# CH32H415REU6-R0.net
KiCad netlist of a schematic drawn in Altium Designer
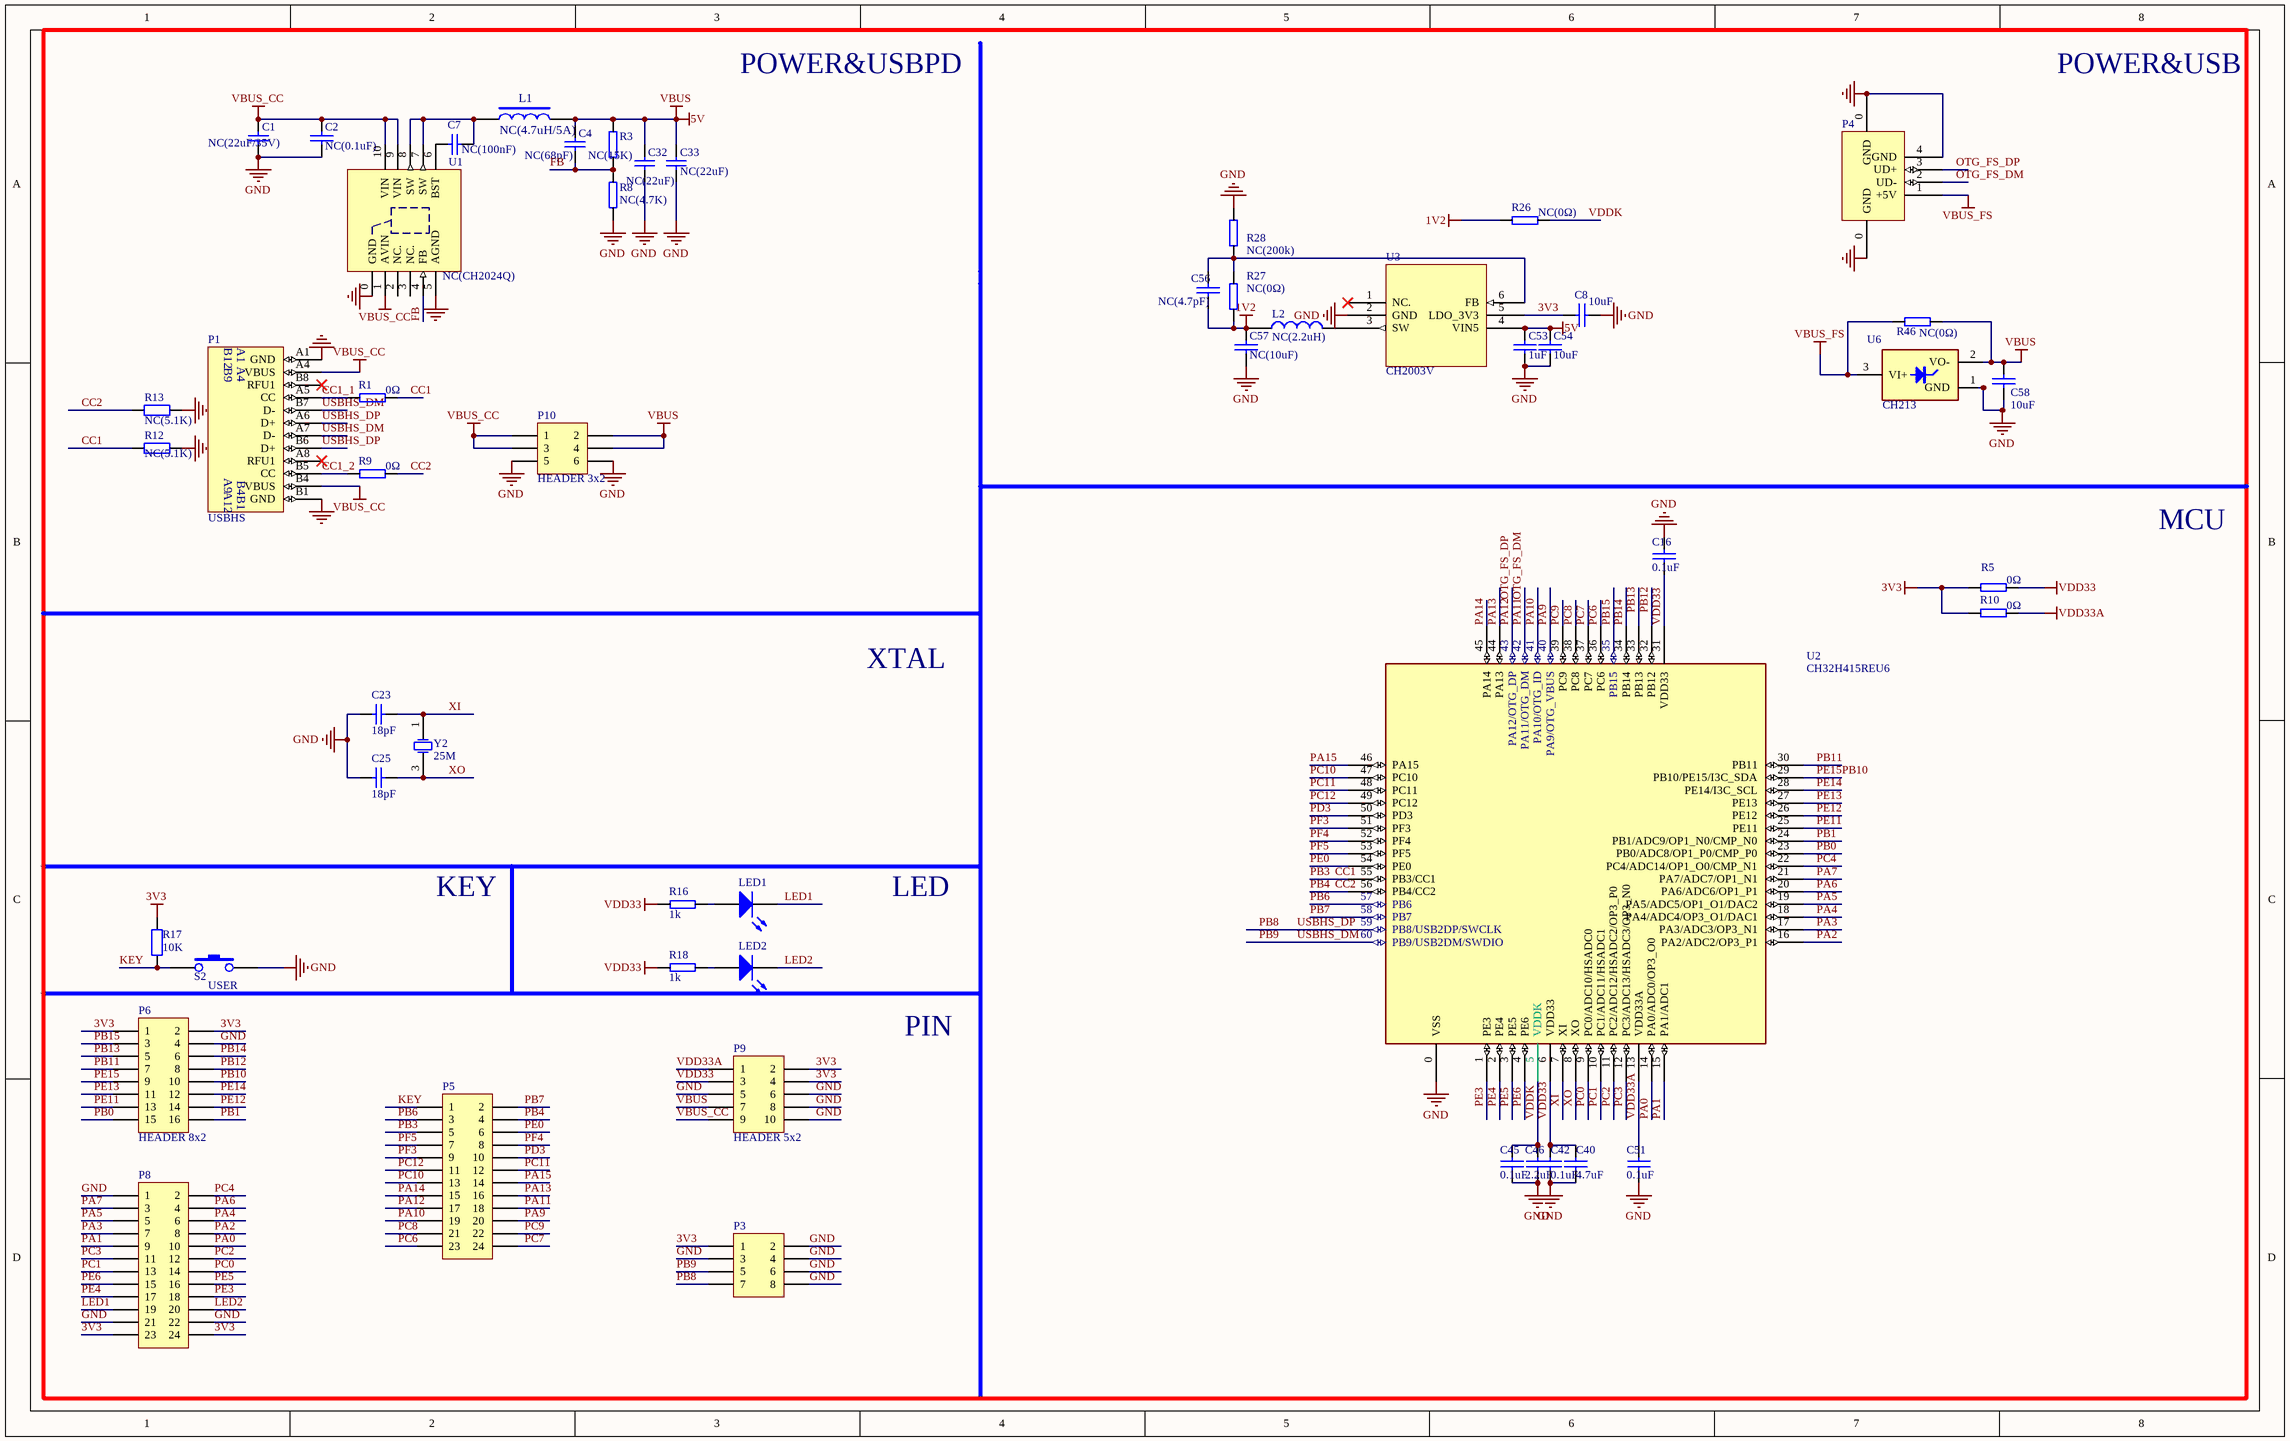
[diagram p0: CH32H415REU6-R0.SchDoc]

(export (version "E")
  (design (tool "Eeschema 10.0.6"))
  (components
    (comp (ref "C1")
      (value "NC(22uF/35V)")
      (footprint "0805_C")
      (description "贴片电容")
      (libsource (lib "Miscellaneous Devices LC") (part "0603 100nF (104) 10% 50V"))
    )
    (comp (ref "C2")
      (value "NC(0.1uF)")
      (footprint "0402_C")
      (description "Capacitor")
      (libsource (lib "") (part "CAP_1"))
    )
    (comp (ref "C4")
      (value "NC(68pF)")
      (footprint "0402_C")
      (description "贴片电容")
      (libsource (lib "Miscellaneous Devices LC") (part "0603 100nF (104) 10% 50V"))
    )
    (comp (ref "C7")
      (value "NC(100nF)")
      (footprint "0603_C")
      (description "贴片电容")
      (libsource (lib "Miscellaneous Devices LC") (part "0603 1uF (105) 10% 50V"))
    )
    (comp (ref "C8")
      (value "10uF")
      (footprint "0603_C")
      (description "Capacitor")
      (libsource (lib "") (part "CAP_1"))
    )
    (comp (ref "C16")
      (value "0.1uF")
      (footprint "0402_C")
      (description "Capacitor")
      (libsource (lib "") (part "CAP_1"))
    )
    (comp (ref "C23")
      (value "18pF")
      (footprint "0402_C")
      (description "Capacitor")
      (libsource (lib "Miscellaneous Devices") (part "Cap"))
    )
    (comp (ref "C25")
      (value "18pF")
      (footprint "0402_C")
      (description "Capacitor")
      (libsource (lib "Miscellaneous Devices") (part "Cap"))
    )
    (comp (ref "C32")
      (value "NC(22uF)")
      (footprint "0805_C")
      (description "贴片电容")
      (libsource (lib "Miscellaneous Devices LC") (part "0603 100nF (104) 10% 50V"))
    )
    (comp (ref "C33")
      (value "NC(22uF)")
      (footprint "0805_C")
      (description "贴片电容")
      (libsource (lib "Miscellaneous Devices LC") (part "0603 100nF (104) 10% 50V"))
    )
    (comp (ref "C40")
      (value "4.7uF")
      (footprint "0402_C")
      (description "Capacitor")
      (libsource (lib "") (part "CAP_1"))
    )
    (comp (ref "C42")
      (value "0.1uF")
      (footprint "0402_C")
      (description "Capacitor")
      (libsource (lib "") (part "CAP_1"))
    )
    (comp (ref "C45")
      (value "0.1uF")
      (footprint "0402_C")
      (description "Capacitor")
      (libsource (lib "") (part "CAP_1"))
    )
    (comp (ref "C46")
      (value "2.2uF")
      (footprint "0402_C")
      (description "Capacitor")
      (libsource (lib "") (part "CAP_1"))
    )
    (comp (ref "C51")
      (value "0.1uF")
      (footprint "0402_C")
      (description "Capacitor")
      (libsource (lib "") (part "CAP_1"))
    )
    (comp (ref "C53")
      (value "1uF")
      (footprint "0402_C")
      (description "Capacitor")
      (libsource (lib "") (part "CAP_2"))
    )
    (comp (ref "C54")
      (value "10uF")
      (footprint "0603_C")
      (description "Capacitor")
      (libsource (lib "") (part "CAP_1"))
    )
    (comp (ref "C56")
      (value "NC(4.7pF)")
      (footprint "0402_C")
      (description "Capacitor")
      (libsource (lib "") (part "CAP_2"))
    )
    (comp (ref "C57")
      (value "NC(10uF)")
      (footprint "0603_C")
      (description "Capacitor")
      (libsource (lib "") (part "CAP_1"))
    )
    (comp (ref "C58")
      (value "10uF")
      (footprint "0603_C")
      (description "Capacitor")
      (libsource (lib "*") (part "CAP"))
    )
    (comp (ref "L1")
      (value "NC(4.7uH/5A)")
      (footprint "SMD_6x6mm")
      (libsource (lib "wch_sch_others") (part "INDUCTOR"))
    )
    (comp (ref "L2") (value "NC(2.2uH)") (footprint "CD32") (libsource (lib "*") (part "INDUCTOR")))
    (comp (ref "LED1")
      (value "LED2  blue")
      (footprint "0603+")
      (description "Typical INFRARED GaAs LED")
      (fields (field (name "PUBLISHER") "Altium Limited"))
      (libsource (lib "Miscellaneous Devices") (part "LED0"))
    )
    (comp (ref "LED2")
      (value "LED1   blue")
      (footprint "0603+")
      (description "Typical INFRARED GaAs LED")
      (fields (field (name "PUBLISHER") "Altium Limited"))
      (libsource (lib "Miscellaneous Devices") (part "LED0"))
    )
    (comp (ref "P1")
      (value "USBHS")
      (footprint "TYPE-C-Receptacle-2.0")
      (libsource (lib "*") (part "TYPE-C1"))
    )
    (comp (ref "P3")
      (value "HEADER 4x2")
      (footprint "MYPCB:IDC8-2.54mm")
      (description "Header, 4-Pin, Dual row")
      (libsource (lib "wch_sch_others") (part "HEADER 4x2"))
    )
    (comp (ref "P4")
      (value "USB_FS")
      (footprint "USBAF")
      (description "USB Port")
      (libsource (lib "*") (part "USB"))
    )
    (comp (ref "P5")
      (value "~")
      (footprint "MYPCB:IDC24-2.54MM")
      (description "Header, 12-Pin, Dual row")
      (libsource (lib "wch_sch_others") (part "HEADER 12x2"))
    )
    (comp (ref "P6")
      (value "HEADER 8x2")
      (footprint "MYPCB:IDC16-2.54mm")
      (description "Header, 8-Pin, Dual row")
      (libsource (lib "wch_sch_others") (part "HEADER 8x2"))
    )
    (comp (ref "P8")
      (value "~")
      (footprint "MYPCB:IDC24-2.54MM")
      (description "Header, 12-Pin, Dual row")
      (libsource (lib "wch_sch_others") (part "HEADER 12x2"))
    )
    (comp (ref "P9")
      (value "HEADER 5x2")
      (footprint "MYPCB:IDC10-2.54mm")
      (description "Header, 5-Pin, Dual row")
      (libsource (lib "wch_sch_others") (part "HEADER 5x2"))
    )
    (comp (ref "P10")
      (value "HEADER 3x2")
      (footprint "MYPCB:IDC6-2.54mm")
      (description "Header, 3-Pin, Dual row")
      (libsource (lib "wch_sch_others") (part "HEADER 3x2"))
    )
    (comp (ref "R1") (value "0Ω") (footprint "0402") (libsource (lib "") (part "RES_1")))
    (comp (ref "R3") (value "NC(15K)") (footprint "0402") (libsource (lib "wch_sch_others(1)") (part "RES")))
    (comp (ref "R5") (value "0Ω") (footprint "0402") (libsource (lib "") (part "RES_1")))
    (comp (ref "R8") (value "NC(4.7K)") (footprint "0402") (libsource (lib "wch_sch_others(1)") (part "RES")))
    (comp (ref "R9") (value "0Ω") (footprint "0402") (libsource (lib "") (part "RES_1")))
    (comp (ref "R10") (value "0Ω") (footprint "0402") (libsource (lib "") (part "RES_1")))
    (comp (ref "R12")
      (value "NC(5.1K)")
      (footprint "0402")
      (description "Resistor")
      (libsource (lib "Miscellaneous Devices") (part "Res2"))
    )
    (comp (ref "R13")
      (value "NC(5.1K)")
      (footprint "0402")
      (description "Resistor")
      (libsource (lib "Miscellaneous Devices") (part "Res2"))
    )
    (comp (ref "R16") (value "1k") (footprint "0402") (libsource (lib "") (part "RES_1")))
    (comp (ref "R17")
      (value "10K")
      (footprint "0402")
      (description "Resistor")
      (libsource (lib "") (part "Res2_1"))
    )
    (comp (ref "R18") (value "1k") (footprint "0402") (libsource (lib "") (part "RES_1")))
    (comp (ref "R26") (value "NC(0Ω)") (footprint "0402") (libsource (lib "") (part "RES_1")))
    (comp (ref "R27") (value "NC(0Ω)") (footprint "0402") (libsource (lib "") (part "RES_1")))
    (comp (ref "R28") (value "NC(200k)") (footprint "0402") (libsource (lib "") (part "RES_1")))
    (comp (ref "R46") (value "NC(0Ω)") (footprint "0402") (libsource (lib "wch_sch_others") (part "RES")))
    (comp (ref "S2")
      (value "USER")
      (footprint "SMD_6.1x3.65x2.5mm-KEY")
      (libsource (lib "wch_sch_others") (part "KEY1"))
    )
    (comp (ref "U1")
      (value "NC(CH2024Q)")
      (footprint "DFN10_3X3")
      (description "Step-Down DC-DC Converter, 28V input, FB 1.2V, 3A output")
      (libsource (lib "DHXXXSCH") (part "CH2024Q"))
    )
    (comp (ref "U2")
      (value "CH32H415REU6")
      (footprint "QFN60_6X6")
      (description "RISC-V FPU HD-MCU, 400MHz, USB2.0 & PD, OPA, ADC, DAC")
      (libsource (lib "DHXXXSCH111") (part "CH32H415REU6"))
    )
    (comp (ref "U3")
      (value "CH2003V")
      (footprint "SOT-23-6")
      (description "Step-Down DC-DC Converter, 5V input, FB 0.6V, 800mA output, with LDO 3.3V * 200mA")
      (libsource (lib "DHXXXSCH") (part "CH2003K"))
    )
    (comp (ref "U6")
      (value "CH213")
      (footprint "SOT-23-3")
      (description "Ideal Diode 5V*1A")
      (libsource (lib "CHXXX") (part "CH213E"))
    )
    (comp (ref "Y2")
      (value "25M")
      (footprint "XT3225")
      (description "Crystal Oscillator")
      (fields (field (name "PUBLISHER") "Altium Limited"))
      (libsource (lib "Miscellaneous Devices") (part "XTAL"))
    )
  )
  (nets
    (net (code "2") (name "/CC1") (class "Default")
      (node (ref "P5") (pin "5") (pinfunction "5_5") (pintype "passive"))
      (node (ref "R1") (pin "1") (pintype "passive"))
      (node (ref "R12") (pin "1") (pinfunction "1_1") (pintype "passive"))
      (node (ref "U2") (pin "55") (pinfunction "PB3/CC1_55") (pintype "bidirectional"))
    )
    (net (code "3") (name "/CC1_1") (class "Default")
      (node (ref "P1") (pin "A5") (pinfunction "CC_A5") (pintype "bidirectional"))
      (node (ref "R1") (pin "2") (pintype "passive"))
    )
    (net (code "4") (name "/CC1_2") (class "Default")
      (node (ref "P1") (pin "B5") (pinfunction "CC_B5") (pintype "bidirectional"))
      (node (ref "R9") (pin "2") (pintype "passive"))
    )
    (net (code "5") (name "/CC2") (class "Default")
      (node (ref "P5") (pin "4") (pinfunction "4_4") (pintype "passive"))
      (node (ref "R13") (pin "1") (pinfunction "1_1") (pintype "passive"))
      (node (ref "R9") (pin "1") (pintype "passive"))
      (node (ref "U2") (pin "56") (pinfunction "PB4/CC2_56") (pintype "bidirectional"))
    )
    (net (code "6") (name "/FB") (class "Default")
      (node (ref "C4") (pin "2") (pinfunction "2_2") (pintype "passive"))
      (node (ref "R3") (pin "1") (pintype "passive"))
      (node (ref "R8") (pin "2") (pintype "passive"))
      (node (ref "U1") (pin "4") (pinfunction "FB_4") (pintype "input"))
    )
    (net (code "7") (name "/KEY") (class "Default")
      (node (ref "P5") (pin "1") (pinfunction "1_1") (pintype "passive"))
      (node (ref "R17") (pin "2") (pinfunction "2_2") (pintype "passive"))
      (node (ref "S2") (pin "1") (pinfunction "1_1") (pintype "passive"))
    )
    (net (code "8") (name "/LED1") (class "Default")
      (node (ref "LED1") (pin "2") (pinfunction "K_2") (pintype "passive"))
      (node (ref "P8") (pin "19") (pinfunction "19_19") (pintype "passive"))
    )
    (net (code "9") (name "/LED2") (class "Default")
      (node (ref "LED2") (pin "2") (pinfunction "K_2") (pintype "passive"))
      (node (ref "P8") (pin "20") (pinfunction "20_20") (pintype "passive"))
    )
    (net (code "10") (name "/OTG_FS_DM") (class "Default")
      (node (ref "P4") (pin "2") (pinfunction "UD-_2") (pintype "bidirectional"))
      (node (ref "P5") (pin "18") (pinfunction "18_18") (pintype "passive"))
      (node (ref "U2") (pin "42") (pinfunction "PA11/OTG_DM_42") (pintype "bidirectional"))
    )
    (net (code "11") (name "/OTG_FS_DP") (class "Default")
      (node (ref "P4") (pin "3") (pinfunction "UD+_3") (pintype "bidirectional"))
      (node (ref "P5") (pin "17") (pinfunction "17_17") (pintype "passive"))
      (node (ref "U2") (pin "43") (pinfunction "PA12/OTG_DP_43") (pintype "bidirectional"))
    )
    (net (code "12") (name "/PA0") (class "Default")
      (node (ref "P8") (pin "10") (pinfunction "10_10") (pintype "passive"))
      (node (ref "U2") (pin "14") (pinfunction "PA0/ADC0/OP3_O0_14") (pintype "bidirectional"))
    )
    (net (code "13") (name "/PA1") (class "Default")
      (node (ref "P8") (pin "9") (pinfunction "9_9") (pintype "passive"))
      (node (ref "U2") (pin "15") (pinfunction "PA1/ADC1_15") (pintype "bidirectional"))
    )
    (net (code "14") (name "/PA2") (class "Default")
      (node (ref "P8") (pin "8") (pinfunction "8_8") (pintype "passive"))
      (node (ref "U2") (pin "16") (pinfunction "PA2/ADC2/OP3_P1_16") (pintype "bidirectional"))
    )
    (net (code "15") (name "/PA3") (class "Default")
      (node (ref "P8") (pin "7") (pinfunction "7_7") (pintype "passive"))
      (node (ref "U2") (pin "17") (pinfunction "PA3/ADC3/OP3_N1_17") (pintype "bidirectional"))
    )
    (net (code "16") (name "/PA4") (class "Default")
      (node (ref "P8") (pin "6") (pinfunction "6_6") (pintype "passive"))
      (node (ref "U2") (pin "18") (pinfunction "PA4/ADC4/OP3_O1/DAC1_18") (pintype "bidirectional"))
    )
    (net (code "17") (name "/PA5") (class "Default")
      (node (ref "P8") (pin "5") (pinfunction "5_5") (pintype "passive"))
      (node (ref "U2") (pin "19") (pinfunction "PA5/ADC5/OP1_O1/DAC2_19") (pintype "bidirectional"))
    )
    (net (code "18") (name "/PA6") (class "Default")
      (node (ref "P8") (pin "4") (pinfunction "4_4") (pintype "passive"))
      (node (ref "U2") (pin "20") (pinfunction "PA6/ADC6/OP1_P1_20") (pintype "bidirectional"))
    )
    (net (code "19") (name "/PA7") (class "Default")
      (node (ref "P8") (pin "3") (pinfunction "3_3") (pintype "passive"))
      (node (ref "U2") (pin "21") (pinfunction "PA7/ADC7/OP1_N1_21") (pintype "bidirectional"))
    )
    (net (code "20") (name "/PA9") (class "Default")
      (node (ref "P5") (pin "20") (pinfunction "20_20") (pintype "passive"))
      (node (ref "U2") (pin "40") (pinfunction "PA9/OTG_VBUS_40") (pintype "bidirectional"))
    )
    (net (code "21") (name "/PA10") (class "Default")
      (node (ref "P5") (pin "19") (pinfunction "19_19") (pintype "passive"))
      (node (ref "U2") (pin "41") (pinfunction "PA10/OTG_ID_41") (pintype "bidirectional"))
    )
    (net (code "22") (name "/PA13") (class "Default")
      (node (ref "P5") (pin "16") (pinfunction "16_16") (pintype "passive"))
      (node (ref "U2") (pin "44") (pinfunction "PA13_44") (pintype "bidirectional"))
    )
    (net (code "23") (name "/PA14") (class "Default")
      (node (ref "P5") (pin "15") (pinfunction "15_15") (pintype "passive"))
      (node (ref "U2") (pin "45") (pinfunction "PA14_45") (pintype "bidirectional"))
    )
    (net (code "24") (name "/PA15") (class "Default")
      (node (ref "P5") (pin "14") (pinfunction "14_14") (pintype "passive"))
      (node (ref "U2") (pin "46") (pinfunction "PA15_46") (pintype "bidirectional"))
    )
    (net (code "25") (name "/PB0") (class "Default")
      (node (ref "P6") (pin "15") (pinfunction "15_15") (pintype "passive"))
      (node (ref "U2") (pin "23") (pinfunction "PB0/ADC8/OP1_P0/CMP_P0_23") (pintype "bidirectional"))
    )
    (net (code "26") (name "/PB1") (class "Default")
      (node (ref "P6") (pin "16") (pinfunction "16_16") (pintype "passive"))
      (node (ref "U2") (pin "24") (pinfunction "PB1/ADC9/OP1_N0/CMP_N0_24") (pintype "bidirectional"))
    )
    (net (code "27") (name "/PB6") (class "Default")
      (node (ref "P5") (pin "3") (pinfunction "3_3") (pintype "passive"))
      (node (ref "U2") (pin "57") (pinfunction "PB6_57") (pintype "bidirectional"))
    )
    (net (code "28") (name "/PB7") (class "Default")
      (node (ref "P5") (pin "2") (pinfunction "2_2") (pintype "passive"))
      (node (ref "U2") (pin "58") (pinfunction "PB7_58") (pintype "bidirectional"))
    )
    (net (code "29") (name "/PB8") (class "Default")
      (node (ref "P1") (pin "A6") (pinfunction "D+_A6") (pintype "bidirectional"))
      (node (ref "P1") (pin "B6") (pinfunction "D+_B6") (pintype "bidirectional"))
      (node (ref "P3") (pin "7") (pinfunction "7_7") (pintype "passive"))
      (node (ref "U2") (pin "59") (pinfunction "PB8/USB2DP/SWCLK_59") (pintype "bidirectional"))
    )
    (net (code "30") (name "/PB9") (class "Default")
      (node (ref "P1") (pin "A7") (pinfunction "D-_A7") (pintype "bidirectional"))
      (node (ref "P1") (pin "B7") (pinfunction "D-_B7") (pintype "bidirectional"))
      (node (ref "P3") (pin "5") (pinfunction "5_5") (pintype "passive"))
      (node (ref "U2") (pin "60") (pinfunction "PB9/USB2DM/SWDIO_60") (pintype "bidirectional"))
    )
    (net (code "31") (name "/PB10") (class "Default")
      (node (ref "P6") (pin "10") (pinfunction "10_10") (pintype "passive"))
      (node (ref "P6") (pin "9") (pinfunction "9_9") (pintype "passive"))
      (node (ref "U2") (pin "29") (pinfunction "PB10/PE15/I3C_SDA_29") (pintype "bidirectional"))
    )
    (net (code "32") (name "/PB11") (class "Default")
      (node (ref "P6") (pin "7") (pinfunction "7_7") (pintype "passive"))
      (node (ref "U2") (pin "30") (pinfunction "PB11_30") (pintype "bidirectional"))
    )
    (net (code "33") (name "/PB12") (class "Default")
      (node (ref "P6") (pin "8") (pinfunction "8_8") (pintype "passive"))
      (node (ref "U2") (pin "32") (pinfunction "PB12_32") (pintype "bidirectional"))
    )
    (net (code "34") (name "/PB13") (class "Default")
      (node (ref "P6") (pin "5") (pinfunction "5_5") (pintype "passive"))
      (node (ref "U2") (pin "33") (pinfunction "PB13_33") (pintype "bidirectional"))
    )
    (net (code "35") (name "/PB14") (class "Default")
      (node (ref "P6") (pin "6") (pinfunction "6_6") (pintype "passive"))
      (node (ref "U2") (pin "34") (pinfunction "PB14_34") (pintype "bidirectional"))
    )
    (net (code "36") (name "/PB15") (class "Default")
      (node (ref "P6") (pin "3") (pinfunction "3_3") (pintype "passive"))
      (node (ref "U2") (pin "35") (pinfunction "PB15_35") (pintype "bidirectional"))
    )
    (net (code "37") (name "/PC0") (class "Default")
      (node (ref "P8") (pin "14") (pinfunction "14_14") (pintype "passive"))
      (node (ref "U2") (pin "9") (pinfunction "PC0/ADC10/HSADC0_9") (pintype "bidirectional"))
    )
    (net (code "38") (name "/PC1") (class "Default")
      (node (ref "P8") (pin "13") (pinfunction "13_13") (pintype "passive"))
      (node (ref "U2") (pin "10") (pinfunction "PC1/ADC11/HSADC1_10") (pintype "bidirectional"))
    )
    (net (code "39") (name "/PC2") (class "Default")
      (node (ref "P8") (pin "12") (pinfunction "12_12") (pintype "passive"))
      (node (ref "U2") (pin "11") (pinfunction "PC2/ADC12/HSADC2/OP3_P0_11") (pintype "bidirectional"))
    )
    (net (code "40") (name "/PC3") (class "Default")
      (node (ref "P8") (pin "11") (pinfunction "11_11") (pintype "passive"))
      (node (ref "U2") (pin "12") (pinfunction "PC3/ADC13/HSADC3/OP3_N0_12") (pintype "bidirectional"))
    )
    (net (code "41") (name "/PC4") (class "Default")
      (node (ref "P8") (pin "2") (pinfunction "2_2") (pintype "passive"))
      (node (ref "U2") (pin "22") (pinfunction "PC4/ADC14/OP1_O0/CMP_N1_22") (pintype "bidirectional"))
    )
    (net (code "42") (name "/PC6") (class "Default")
      (node (ref "P5") (pin "23") (pinfunction "23_23") (pintype "passive"))
      (node (ref "U2") (pin "36") (pinfunction "PC6_36") (pintype "bidirectional"))
    )
    (net (code "43") (name "/PC7") (class "Default")
      (node (ref "P5") (pin "24") (pinfunction "24_24") (pintype "passive"))
      (node (ref "U2") (pin "37") (pinfunction "PC7_37") (pintype "bidirectional"))
    )
    (net (code "44") (name "/PC8") (class "Default")
      (node (ref "P5") (pin "21") (pinfunction "21_21") (pintype "passive"))
      (node (ref "U2") (pin "38") (pinfunction "PC8_38") (pintype "bidirectional"))
    )
    (net (code "45") (name "/PC9") (class "Default")
      (node (ref "P5") (pin "22") (pinfunction "22_22") (pintype "passive"))
      (node (ref "U2") (pin "39") (pinfunction "PC9_39") (pintype "bidirectional"))
    )
    (net (code "46") (name "/PC10") (class "Default")
      (node (ref "P5") (pin "13") (pinfunction "13_13") (pintype "passive"))
      (node (ref "U2") (pin "47") (pinfunction "PC10_47") (pintype "bidirectional"))
    )
    (net (code "47") (name "/PC11") (class "Default")
      (node (ref "P5") (pin "12") (pinfunction "12_12") (pintype "passive"))
      (node (ref "U2") (pin "48") (pinfunction "PC11_48") (pintype "bidirectional"))
    )
    (net (code "48") (name "/PC12") (class "Default")
      (node (ref "P5") (pin "11") (pinfunction "11_11") (pintype "passive"))
      (node (ref "U2") (pin "49") (pinfunction "PC12_49") (pintype "bidirectional"))
    )
    (net (code "49") (name "/PD3") (class "Default")
      (node (ref "P5") (pin "10") (pinfunction "10_10") (pintype "passive"))
      (node (ref "U2") (pin "50") (pinfunction "PD3_50") (pintype "bidirectional"))
    )
    (net (code "50") (name "/PE0") (class "Default")
      (node (ref "P5") (pin "6") (pinfunction "6_6") (pintype "passive"))
      (node (ref "U2") (pin "54") (pinfunction "PE0_54") (pintype "bidirectional"))
    )
    (net (code "51") (name "/PE3") (class "Default")
      (node (ref "P8") (pin "18") (pinfunction "18_18") (pintype "passive"))
      (node (ref "U2") (pin "1") (pinfunction "PE3_1") (pintype "bidirectional"))
    )
    (net (code "52") (name "/PE4") (class "Default")
      (node (ref "P8") (pin "17") (pinfunction "17_17") (pintype "passive"))
      (node (ref "U2") (pin "2") (pinfunction "PE4_2") (pintype "bidirectional"))
    )
    (net (code "53") (name "/PE5") (class "Default")
      (node (ref "P8") (pin "16") (pinfunction "16_16") (pintype "passive"))
      (node (ref "U2") (pin "3") (pinfunction "PE5_3") (pintype "bidirectional"))
    )
    (net (code "54") (name "/PE6") (class "Default")
      (node (ref "P8") (pin "15") (pinfunction "15_15") (pintype "passive"))
      (node (ref "U2") (pin "4") (pinfunction "PE6_4") (pintype "bidirectional"))
    )
    (net (code "55") (name "/PE11") (class "Default")
      (node (ref "P6") (pin "13") (pinfunction "13_13") (pintype "passive"))
      (node (ref "U2") (pin "25") (pinfunction "PE11_25") (pintype "bidirectional"))
    )
    (net (code "56") (name "/PE12") (class "Default")
      (node (ref "P6") (pin "14") (pinfunction "14_14") (pintype "passive"))
      (node (ref "U2") (pin "26") (pinfunction "PE12_26") (pintype "bidirectional"))
    )
    (net (code "57") (name "/PE13") (class "Default")
      (node (ref "P6") (pin "11") (pinfunction "11_11") (pintype "passive"))
      (node (ref "U2") (pin "27") (pinfunction "PE13_27") (pintype "bidirectional"))
    )
    (net (code "58") (name "/PE14") (class "Default")
      (node (ref "P6") (pin "12") (pinfunction "12_12") (pintype "passive"))
      (node (ref "U2") (pin "28") (pinfunction "PE14/I3C_SCL_28") (pintype "bidirectional"))
    )
    (net (code "59") (name "/PF3") (class "Default")
      (node (ref "P5") (pin "9") (pinfunction "9_9") (pintype "passive"))
      (node (ref "U2") (pin "51") (pinfunction "PF3_51") (pintype "bidirectional"))
    )
    (net (code "60") (name "/PF4") (class "Default")
      (node (ref "P5") (pin "8") (pinfunction "8_8") (pintype "passive"))
      (node (ref "U2") (pin "52") (pinfunction "PF4_52") (pintype "bidirectional"))
    )
    (net (code "61") (name "/PF5") (class "Default")
      (node (ref "P5") (pin "7") (pinfunction "7_7") (pintype "passive"))
      (node (ref "U2") (pin "53") (pinfunction "PF5_53") (pintype "bidirectional"))
    )
    (net (code "62") (name "/VDDK") (class "Default")
      (node (ref "C45") (pin "2") (pinfunction "2_2") (pintype "passive"))
      (node (ref "C46") (pin "1") (pinfunction "1_1") (pintype "passive"))
      (node (ref "R26") (pin "1") (pintype "passive"))
      (node (ref "U2") (pin "5") (pinfunction "VDDK_5") (pintype "power_in"))
    )
    (net (code "63") (name "/XI") (class "Default")
      (node (ref "C23") (pin "2") (pinfunction "2_2") (pintype "passive"))
      (node (ref "U2") (pin "7") (pinfunction "XI_7") (pintype "bidirectional"))
      (node (ref "Y2") (pin "1") (pinfunction "OSC1_1") (pintype "passive"))
    )
    (net (code "64") (name "/XO") (class "Default")
      (node (ref "C25") (pin "2") (pinfunction "2_2") (pintype "passive"))
      (node (ref "U2") (pin "8") (pinfunction "XO_8") (pintype "bidirectional"))
      (node (ref "Y2") (pin "3") (pinfunction "OSC2_3") (pintype "passive"))
    )
    (net (code "65") (name "1V2") (class "Default")
      (node (ref "C56") (pin "1") (pinfunction "1_1") (pintype "passive"))
      (node (ref "C57") (pin "2") (pinfunction "2_2") (pintype "passive"))
      (node (ref "L2") (pin "2") (pinfunction "2_2") (pintype "passive"))
      (node (ref "R26") (pin "2") (pintype "passive"))
      (node (ref "R27") (pin "1") (pintype "passive"))
    )
    (net (code "66") (name "3V3") (class "Default")
      (node (ref "C8") (pin "2") (pinfunction "2_2") (pintype "passive"))
      (node (ref "P3") (pin "1") (pinfunction "1_1") (pintype "passive"))
      (node (ref "P6") (pin "1") (pinfunction "1_1") (pintype "passive"))
      (node (ref "P6") (pin "2") (pinfunction "2_2") (pintype "passive"))
      (node (ref "P8") (pin "23") (pinfunction "23_23") (pintype "passive"))
      (node (ref "P8") (pin "24") (pinfunction "24_24") (pintype "passive"))
      (node (ref "P9") (pin "2") (pinfunction "2_2") (pintype "passive"))
      (node (ref "P9") (pin "4") (pinfunction "4_4") (pintype "passive"))
      (node (ref "R10") (pin "2") (pintype "passive"))
      (node (ref "R17") (pin "1") (pinfunction "1_1") (pintype "passive"))
      (node (ref "R5") (pin "2") (pintype "passive"))
      (node (ref "U3") (pin "5") (pinfunction "LDO_3V3_5") (pintype "power_in"))
    )
    (net (code "67") (name "5V") (class "Default")
      (node (ref "C32") (pin "2") (pinfunction "2_2") (pintype "passive"))
      (node (ref "C33") (pin "2") (pinfunction "2_2") (pintype "passive"))
      (node (ref "C4") (pin "1") (pinfunction "1_1") (pintype "passive"))
      (node (ref "C53") (pin "2") (pinfunction "2_2") (pintype "passive"))
      (node (ref "C54") (pin "2") (pinfunction "2_2") (pintype "passive"))
      (node (ref "C58") (pin "1") (pinfunction "1_1") (pintype "passive"))
      (node (ref "L1") (pin "2") (pinfunction "2_2") (pintype "passive"))
      (node (ref "P10") (pin "2") (pinfunction "2_2") (pintype "passive"))
      (node (ref "P10") (pin "4") (pinfunction "4_4") (pintype "passive"))
      (node (ref "P9") (pin "7") (pinfunction "7_7") (pintype "passive"))
      (node (ref "R3") (pin "2") (pintype "passive"))
      (node (ref "R46") (pin "1") (pintype "passive"))
      (node (ref "U3") (pin "4") (pinfunction "VIN5_4") (pintype "power_in"))
      (node (ref "U6") (pin "2") (pinfunction "VO-_2") (pintype "power_in"))
    )
    (net (code "68") (name "GND") (class "Default")
      (node (ref "C1") (pin "1") (pinfunction "1_1") (pintype "passive"))
      (node (ref "C16") (pin "2") (pinfunction "2_2") (pintype "passive"))
      (node (ref "C2") (pin "1") (pinfunction "1_1") (pintype "passive"))
      (node (ref "C23") (pin "1") (pinfunction "1_1") (pintype "passive"))
      (node (ref "C25") (pin "1") (pinfunction "1_1") (pintype "passive"))
      (node (ref "C32") (pin "1") (pinfunction "1_1") (pintype "passive"))
      (node (ref "C33") (pin "1") (pinfunction "1_1") (pintype "passive"))
      (node (ref "C40") (pin "1") (pinfunction "1_1") (pintype "passive"))
      (node (ref "C42") (pin "1") (pinfunction "1_1") (pintype "passive"))
      (node (ref "C45") (pin "1") (pinfunction "1_1") (pintype "passive"))
      (node (ref "C46") (pin "2") (pinfunction "2_2") (pintype "passive"))
      (node (ref "C51") (pin "1") (pinfunction "1_1") (pintype "passive"))
      (node (ref "C53") (pin "1") (pinfunction "1_1") (pintype "passive"))
      (node (ref "C54") (pin "1") (pinfunction "1_1") (pintype "passive"))
      (node (ref "C57") (pin "1") (pinfunction "1_1") (pintype "passive"))
      (node (ref "C58") (pin "2") (pinfunction "2_2") (pintype "passive"))
      (node (ref "C8") (pin "1") (pinfunction "1_1") (pintype "passive"))
      (node (ref "P1") (pin "A1") (pinfunction "GND_A1") (pintype "bidirectional"))
      (node (ref "P1") (pin "B1") (pinfunction "GND_B1") (pintype "bidirectional"))
      (node (ref "P10") (pin "5") (pinfunction "5_5") (pintype "passive"))
      (node (ref "P10") (pin "6") (pinfunction "6_6") (pintype "passive"))
      (node (ref "P3") (pin "2") (pinfunction "2_2") (pintype "passive"))
      (node (ref "P3") (pin "3") (pinfunction "3_3") (pintype "passive"))
      (node (ref "P3") (pin "4") (pinfunction "4_4") (pintype "passive"))
      (node (ref "P3") (pin "6") (pinfunction "6_6") (pintype "passive"))
      (node (ref "P3") (pin "8") (pinfunction "8_8") (pintype "passive"))
      (node (ref "P4") (pin "0") (pinfunction "GND_0") (pintype "power_in"))
      (node (ref "P4") (pin "4") (pinfunction "GND_4") (pintype "power_in"))
      (node (ref "P6") (pin "4") (pinfunction "4_4") (pintype "passive"))
      (node (ref "P8") (pin "1") (pinfunction "1_1") (pintype "passive"))
      (node (ref "P8") (pin "21") (pinfunction "21_21") (pintype "passive"))
      (node (ref "P8") (pin "22") (pinfunction "22_22") (pintype "passive"))
      (node (ref "P9") (pin "10") (pinfunction "10_10") (pintype "passive"))
      (node (ref "P9") (pin "5") (pinfunction "5_5") (pintype "passive"))
      (node (ref "P9") (pin "6") (pinfunction "6_6") (pintype "passive"))
      (node (ref "P9") (pin "8") (pinfunction "8_8") (pintype "passive"))
      (node (ref "R12") (pin "2") (pinfunction "2_2") (pintype "passive"))
      (node (ref "R13") (pin "2") (pinfunction "2_2") (pintype "passive"))
      (node (ref "R28") (pin "2") (pintype "passive"))
      (node (ref "R8") (pin "1") (pintype "passive"))
      (node (ref "S2") (pin "2") (pinfunction "2_2") (pintype "passive"))
      (node (ref "U1") (pin "0") (pinfunction "GND_0") (pintype "power_in"))
      (node (ref "U1") (pin "5") (pinfunction "AGND_5") (pintype "power_in"))
      (node (ref "U2") (pin "0") (pinfunction "VSS_0") (pintype "power_in"))
      (node (ref "U3") (pin "2") (pinfunction "GND_2") (pintype "power_in"))
      (node (ref "U6") (pin "1") (pinfunction "GND_1") (pintype "power_in"))
    )
    (net (code "69") (name "Net-(C7-Pad2)") (class "Default")
      (node (ref "C7") (pin "2") (pinfunction "2_2") (pintype "passive"))
      (node (ref "L1") (pin "1") (pinfunction "1_1") (pintype "passive"))
      (node (ref "U1") (pin "7") (pinfunction "SW_7") (pintype "output"))
      (node (ref "U1") (pin "8") (pinfunction "SW_8") (pintype "output"))
    )
    (net (code "70") (name "Net-(LED1-A)") (class "Default")
      (node (ref "LED1") (pin "1") (pinfunction "A_1") (pintype "passive"))
      (node (ref "R16") (pin "2") (pintype "passive"))
    )
    (net (code "71") (name "Net-(LED2-A)") (class "Default")
      (node (ref "LED2") (pin "1") (pinfunction "A_1") (pintype "passive"))
      (node (ref "R18") (pin "2") (pintype "passive"))
    )
    (net (code "72") (name "Net-(U1-BST)") (class "Default")
      (node (ref "C7") (pin "1") (pinfunction "1_1") (pintype "passive"))
      (node (ref "U1") (pin "6") (pinfunction "BST_6") (pintype "power_in"))
    )
    (net (code "73") (name "Net-(U3-FB)") (class "Default")
      (node (ref "C56") (pin "2") (pinfunction "2_2") (pintype "passive"))
      (node (ref "R27") (pin "2") (pintype "passive"))
      (node (ref "R28") (pin "1") (pintype "passive"))
      (node (ref "U3") (pin "6") (pinfunction "FB_6") (pintype "input"))
    )
    (net (code "74") (name "Net-(U3-SW)") (class "Default")
      (node (ref "L2") (pin "1") (pinfunction "1_1") (pintype "passive"))
      (node (ref "U3") (pin "3") (pinfunction "SW_3") (pintype "output"))
    )
    (net (code "75") (name "VBUS_CC") (class "Default")
      (node (ref "C1") (pin "2") (pinfunction "2_2") (pintype "passive"))
      (node (ref "C2") (pin "2") (pinfunction "2_2") (pintype "passive"))
      (node (ref "P1") (pin "A4") (pinfunction "VBUS_A4") (pintype "bidirectional"))
      (node (ref "P1") (pin "B4") (pinfunction "VBUS_B4") (pintype "bidirectional"))
      (node (ref "P10") (pin "1") (pinfunction "1_1") (pintype "passive"))
      (node (ref "P10") (pin "3") (pinfunction "3_3") (pintype "passive"))
      (node (ref "P9") (pin "9") (pinfunction "9_9") (pintype "passive"))
      (node (ref "U1") (pin "1") (pinfunction "AVIN_1") (pintype "power_in"))
      (node (ref "U1") (pin "10") (pinfunction "VIN_10") (pintype "power_in"))
      (node (ref "U1") (pin "9") (pinfunction "VIN_9") (pintype "power_in"))
    )
    (net (code "76") (name "VBUS_FS") (class "Default")
      (node (ref "P4") (pin "1") (pinfunction "+5V_1") (pintype "power_in"))
      (node (ref "R46") (pin "2") (pintype "passive"))
      (node (ref "U6") (pin "3") (pinfunction "VI+_3") (pintype "power_in"))
    )
    (net (code "77") (name "VDD33") (class "Default")
      (node (ref "C16") (pin "1") (pinfunction "1_1") (pintype "passive"))
      (node (ref "C40") (pin "2") (pinfunction "2_2") (pintype "passive"))
      (node (ref "C42") (pin "2") (pinfunction "2_2") (pintype "passive"))
      (node (ref "P9") (pin "3") (pinfunction "3_3") (pintype "passive"))
      (node (ref "R16") (pin "1") (pintype "passive"))
      (node (ref "R18") (pin "1") (pintype "passive"))
      (node (ref "R5") (pin "1") (pintype "passive"))
      (node (ref "U2") (pin "31") (pinfunction "VDD33_31") (pintype "power_in"))
      (node (ref "U2") (pin "6") (pinfunction "VDD33_6") (pintype "power_in"))
    )
    (net (code "78") (name "VDD33A") (class "Default")
      (node (ref "C51") (pin "2") (pinfunction "2_2") (pintype "passive"))
      (node (ref "P9") (pin "1") (pinfunction "1_1") (pintype "passive"))
      (node (ref "R10") (pin "1") (pintype "passive"))
      (node (ref "U2") (pin "13") (pinfunction "VDD33A_13") (pintype "power_in"))
    )
    (net (code "79") (name "unconnected-(P1-RFU1-PadA8)") (class "Default")
      (node (ref "P1") (pin "A8") (pinfunction "RFU1_A8") (pintype "bidirectional+no_connect"))
    )
    (net (code "80") (name "unconnected-(P1-RFU1-PadB8)") (class "Default")
      (node (ref "P1") (pin "B8") (pinfunction "RFU1_B8") (pintype "bidirectional+no_connect"))
    )
    (net (code "81") (name "unconnected-(U1-NC.-Pad2)") (class "Default")
      (node (ref "U1") (pin "2") (pinfunction "NC._2") (pintype "passive"))
    )
    (net (code "82") (name "unconnected-(U1-NC.-Pad3)") (class "Default")
      (node (ref "U1") (pin "3") (pinfunction "NC._3") (pintype "passive"))
    )
    (net (code "83") (name "unconnected-(U3-NC.-Pad1)") (class "Default")
      (node (ref "U3") (pin "1") (pinfunction "NC._1") (pintype "passive+no_connect"))
    )
  )
)
